# PA_group.net
KiCad netlist of a schematic drawn in Altium Designer
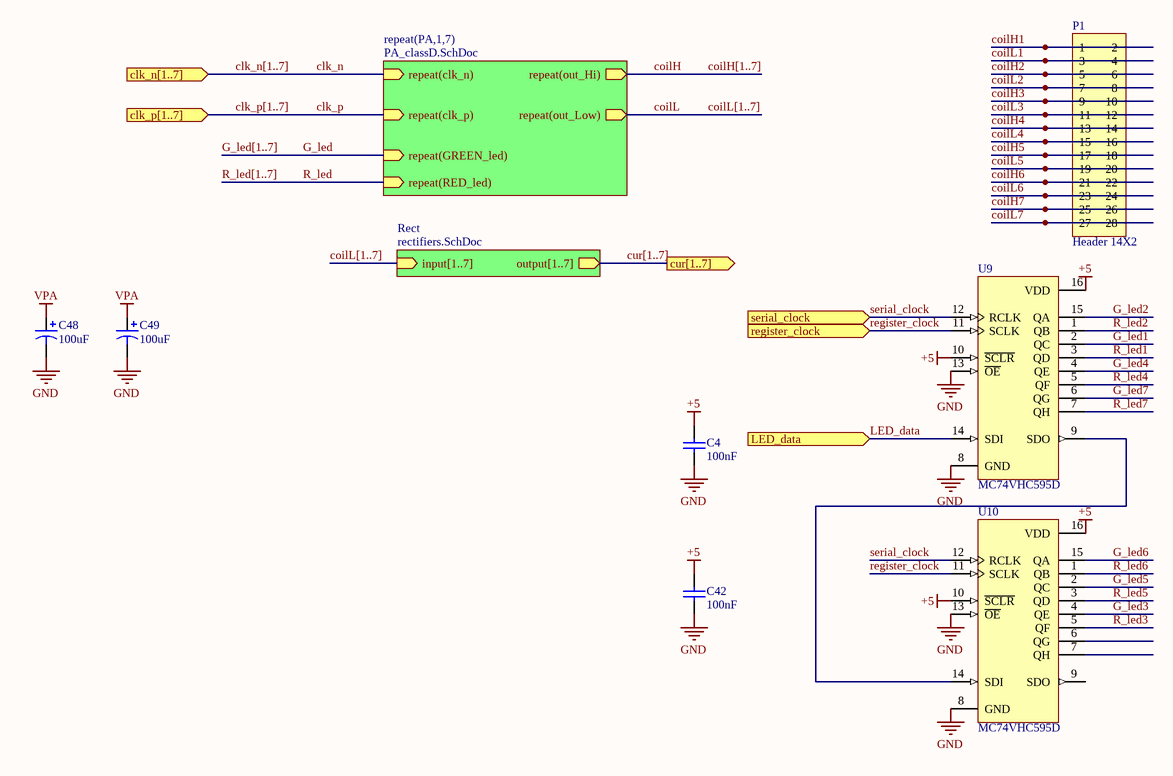
[diagram p0: PA_group.SchDoc]

(export (version "E")
  (design (tool "Eeschema 10.0.6"))
  (components
    (comp (ref "C4")
      (value "100nF")
      (footprint "SMD_CAP_0805")
      (description "CAP-100Nf")
      (fields (field (name "Comment") "Cap"))
      (libsource (lib "Altium library (www.AVRelec.com)") (part "Cap ceramic"))
    )
    (comp (ref "C42")
      (value "100nF")
      (footprint "SMD_CAP_0805")
      (description "CAP-100Nf")
      (fields (field (name "Comment") "Cap"))
      (libsource (lib "Altium library (www.AVRelec.com)") (part "Cap ceramic"))
    )
    (comp (ref "C48")
      (value "100uF")
      (footprint "Cap SMD electrolite-6.3mm")
      (description "Polarized Capacitor (Radial)")
      (fields (field (name "PUBLISHER") "Altium Limited"))
      (libsource (lib "Miscellaneous Devices") (part "Cap Pol1"))
    )
    (comp (ref "C49")
      (value "100uF")
      (footprint "Cap SMD electrolite-6.3mm")
      (description "Polarized Capacitor (Radial)")
      (fields (field (name "PUBLISHER") "Altium Limited"))
      (libsource (lib "Miscellaneous Devices") (part "Cap Pol1"))
    )
    (comp (ref "P1")
      (value "Header 14X2")
      (footprint "HDR2X14")
      (description "Header, 14-Pin, Dual row")
      (fields (field (name "PUBLISHER") "Altium Limited"))
      (libsource (lib "Miscellaneous Connectors") (part "Header 14X2"))
    )
    (comp (ref "U9")
      (value "MC74VHC595D")
      (footprint "751B-05_N")
      (description "8-Bit 3-State Shift Register with Output Storage Register")
      (fields (field (name "PUBLISHER") "Altium Limited"))
      (libsource (lib "ON Semi Logic Register") (part "MC74VHC595D"))
    )
    (comp (ref "U10")
      (value "MC74VHC595D")
      (footprint "751B-05_N")
      (description "8-Bit 3-State Shift Register with Output Storage Register")
      (fields (field (name "PUBLISHER") "Altium Limited"))
      (libsource (lib "ON Semi Logic Register") (part "MC74VHC595D"))
    )
  )
  (nets
    (net (code "22") (name "+5") (class "Default")
      (node (ref "C4") (pin "1") (pinfunction "1_1") (pintype "passive"))
      (node (ref "C42") (pin "1") (pinfunction "1_1") (pintype "passive"))
      (node (ref "U10") (pin "10") (pinfunction "~{SCLR}_10") (pintype "input"))
      (node (ref "U10") (pin "16") (pinfunction "VDD_16") (pintype "power_in"))
      (node (ref "U9") (pin "10") (pinfunction "~{SCLR}_10") (pintype "input"))
      (node (ref "U9") (pin "16") (pinfunction "VDD_16") (pintype "power_in"))
    )
    (net (code "24") (name "/G_led1") (class "Default")
      (node (ref "U9") (pin "2") (pinfunction "QC_2") (pintype "tri_state"))
    )
    (net (code "25") (name "/G_led2") (class "Default")
      (node (ref "U9") (pin "15") (pinfunction "QA_15") (pintype "tri_state"))
    )
    (net (code "26") (name "/G_led3") (class "Default")
      (node (ref "U10") (pin "4") (pinfunction "QE_4") (pintype "tri_state"))
    )
    (net (code "27") (name "/G_led4") (class "Default")
      (node (ref "U9") (pin "4") (pinfunction "QE_4") (pintype "tri_state"))
    )
    (net (code "28") (name "/G_led5") (class "Default")
      (node (ref "U10") (pin "2") (pinfunction "QC_2") (pintype "tri_state"))
    )
    (net (code "29") (name "/G_led6") (class "Default")
      (node (ref "U10") (pin "15") (pinfunction "QA_15") (pintype "tri_state"))
    )
    (net (code "30") (name "/G_led7") (class "Default")
      (node (ref "U9") (pin "6") (pinfunction "QG_6") (pintype "tri_state"))
    )
    (net (code "32") (name "/LED_data") (class "Default")
      (node (ref "U9") (pin "14") (pinfunction "SDI_14") (pintype "input"))
    )
    (net (code "34") (name "/R_led1") (class "Default")
      (node (ref "U9") (pin "3") (pinfunction "QD_3") (pintype "tri_state"))
    )
    (net (code "35") (name "/R_led2") (class "Default")
      (node (ref "U9") (pin "1") (pinfunction "QB_1") (pintype "tri_state"))
    )
    (net (code "36") (name "/R_led3") (class "Default")
      (node (ref "U10") (pin "5") (pinfunction "QF_5") (pintype "tri_state"))
    )
    (net (code "37") (name "/R_led4") (class "Default")
      (node (ref "U9") (pin "5") (pinfunction "QF_5") (pintype "tri_state"))
    )
    (net (code "38") (name "/R_led5") (class "Default")
      (node (ref "U10") (pin "3") (pinfunction "QD_3") (pintype "tri_state"))
    )
    (net (code "39") (name "/R_led6") (class "Default")
      (node (ref "U10") (pin "1") (pinfunction "QB_1") (pintype "tri_state"))
    )
    (net (code "40") (name "/R_led7") (class "Default")
      (node (ref "U9") (pin "7") (pinfunction "QH_7") (pintype "tri_state"))
    )
    (net (code "47") (name "/coilH1") (class "Default")
      (node (ref "P1") (pin "1") (pinfunction "1_1") (pintype "passive"))
      (node (ref "P1") (pin "2") (pinfunction "2_2") (pintype "passive"))
    )
    (net (code "48") (name "/coilH2") (class "Default")
      (node (ref "P1") (pin "5") (pinfunction "5_5") (pintype "passive"))
      (node (ref "P1") (pin "6") (pinfunction "6_6") (pintype "passive"))
    )
    (net (code "49") (name "/coilH3") (class "Default")
      (node (ref "P1") (pin "10") (pinfunction "10_10") (pintype "passive"))
      (node (ref "P1") (pin "9") (pinfunction "9_9") (pintype "passive"))
    )
    (net (code "50") (name "/coilH4") (class "Default")
      (node (ref "P1") (pin "13") (pinfunction "13_13") (pintype "passive"))
      (node (ref "P1") (pin "14") (pinfunction "14_14") (pintype "passive"))
    )
    (net (code "51") (name "/coilH5") (class "Default")
      (node (ref "P1") (pin "17") (pinfunction "17_17") (pintype "passive"))
      (node (ref "P1") (pin "18") (pinfunction "18_18") (pintype "passive"))
    )
    (net (code "52") (name "/coilH6") (class "Default")
      (node (ref "P1") (pin "21") (pinfunction "21_21") (pintype "passive"))
      (node (ref "P1") (pin "22") (pinfunction "22_22") (pintype "passive"))
    )
    (net (code "53") (name "/coilH7") (class "Default")
      (node (ref "P1") (pin "25") (pinfunction "25_25") (pintype "passive"))
      (node (ref "P1") (pin "26") (pinfunction "26_26") (pintype "passive"))
    )
    (net (code "56") (name "/coilL1") (class "Default")
      (node (ref "P1") (pin "3") (pinfunction "3_3") (pintype "passive"))
      (node (ref "P1") (pin "4") (pinfunction "4_4") (pintype "passive"))
    )
    (net (code "57") (name "/coilL2") (class "Default")
      (node (ref "P1") (pin "7") (pinfunction "7_7") (pintype "passive"))
      (node (ref "P1") (pin "8") (pinfunction "8_8") (pintype "passive"))
    )
    (net (code "58") (name "/coilL3") (class "Default")
      (node (ref "P1") (pin "11") (pinfunction "11_11") (pintype "passive"))
      (node (ref "P1") (pin "12") (pinfunction "12_12") (pintype "passive"))
    )
    (net (code "59") (name "/coilL4") (class "Default")
      (node (ref "P1") (pin "15") (pinfunction "15_15") (pintype "passive"))
      (node (ref "P1") (pin "16") (pinfunction "16_16") (pintype "passive"))
    )
    (net (code "60") (name "/coilL5") (class "Default")
      (node (ref "P1") (pin "19") (pinfunction "19_19") (pintype "passive"))
      (node (ref "P1") (pin "20") (pinfunction "20_20") (pintype "passive"))
    )
    (net (code "61") (name "/coilL6") (class "Default")
      (node (ref "P1") (pin "23") (pinfunction "23_23") (pintype "passive"))
      (node (ref "P1") (pin "24") (pinfunction "24_24") (pintype "passive"))
    )
    (net (code "62") (name "/coilL7") (class "Default")
      (node (ref "P1") (pin "27") (pinfunction "27_27") (pintype "passive"))
      (node (ref "P1") (pin "28") (pinfunction "28_28") (pintype "passive"))
    )
    (net (code "65") (name "/register_clock") (class "Default")
      (node (ref "U10") (pin "11") (pinfunction "SCLK_11") (pintype "input"))
      (node (ref "U9") (pin "11") (pinfunction "SCLK_11") (pintype "input"))
    )
    (net (code "66") (name "/serial_clock") (class "Default")
      (node (ref "U10") (pin "12") (pinfunction "RCLK_12") (pintype "input"))
      (node (ref "U9") (pin "12") (pinfunction "RCLK_12") (pintype "input"))
    )
    (net (code "67") (name "GND") (class "Default")
      (node (ref "C4") (pin "2") (pinfunction "2_2") (pintype "passive"))
      (node (ref "C42") (pin "2") (pinfunction "2_2") (pintype "passive"))
      (node (ref "C48") (pin "2") (pinfunction "2_2") (pintype "passive"))
      (node (ref "C49") (pin "2") (pinfunction "2_2") (pintype "passive"))
      (node (ref "U10") (pin "13") (pinfunction "~{OE}_13") (pintype "input"))
      (node (ref "U10") (pin "8") (pinfunction "GND_8") (pintype "power_in"))
      (node (ref "U9") (pin "13") (pinfunction "~{OE}_13") (pintype "input"))
      (node (ref "U9") (pin "8") (pinfunction "GND_8") (pintype "power_in"))
    )
    (net (code "68") (name "Net-(U10-SDI)") (class "Default")
      (node (ref "U10") (pin "14") (pinfunction "SDI_14") (pintype "input"))
      (node (ref "U9") (pin "9") (pinfunction "SDO_9") (pintype "output"))
    )
    (net (code "69") (name "VPA") (class "Default")
      (node (ref "C48") (pin "1") (pinfunction "1_1") (pintype "passive"))
      (node (ref "C49") (pin "1") (pinfunction "1_1") (pintype "passive"))
    )
    (net (code "70") (name "unconnected-(U10-QG-Pad6)") (class "Default")
      (node (ref "U10") (pin "6") (pinfunction "QG_6") (pintype "tri_state"))
    )
    (net (code "71") (name "unconnected-(U10-QH-Pad7)") (class "Default")
      (node (ref "U10") (pin "7") (pinfunction "QH_7") (pintype "tri_state"))
    )
    (net (code "72") (name "unconnected-(U10-SDO-Pad9)") (class "Default")
      (node (ref "U10") (pin "9") (pinfunction "SDO_9") (pintype "output"))
    )
  )
)
